# mbed-enablement-platform_F_3.net
KiCad netlist of a schematic drawn in Altium Designer
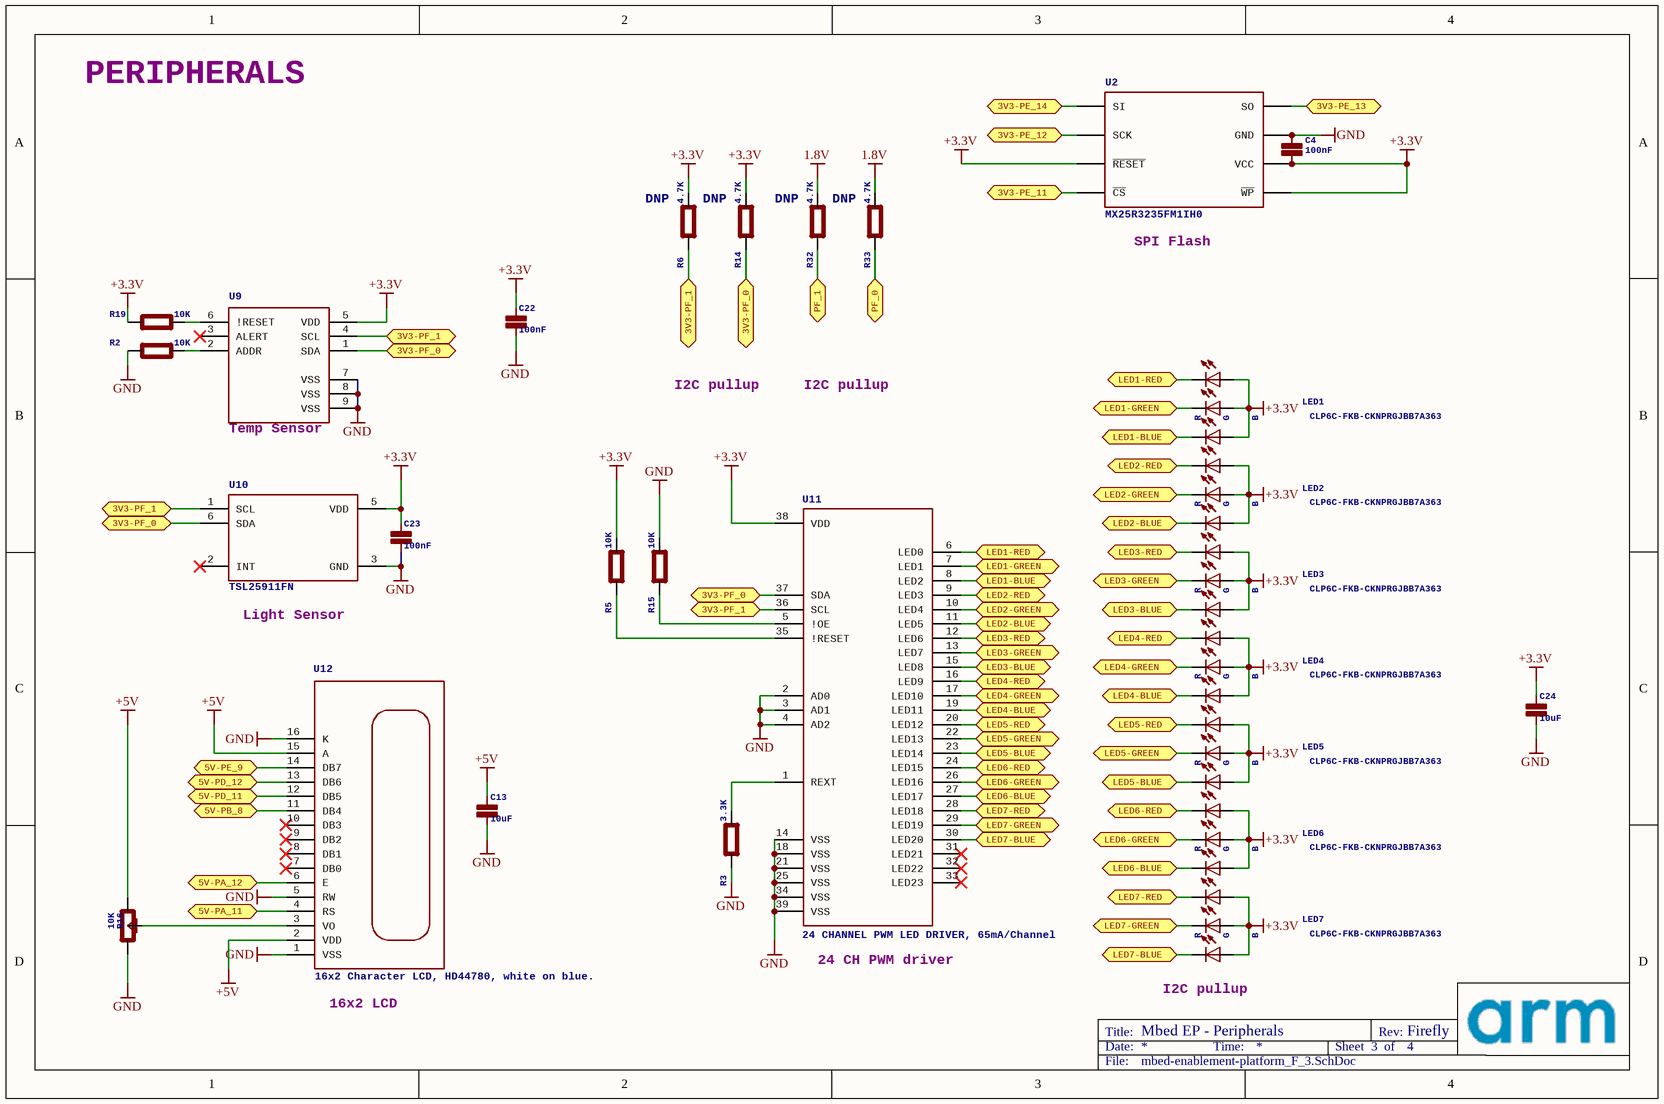
[diagram p0: mbed-enablement-platform_F_3.SchDoc]

(export (version "E")
  (design (tool "Eeschema 10.0.6"))
  (components
    (comp (ref "C4")
      (value "100nF")
      (footprint "0603")
      (description "Capacitor")
      (libsource (lib "mbed-workplace-env-mon") (part "CAPACITOR0603"))
    )
    (comp (ref "C13")
      (value "10uF")
      (footprint "0603")
      (description "Capacitor")
      (libsource (lib "mbed-workplace-env-mon") (part "CAPACITOR0603"))
    )
    (comp (ref "C22")
      (value "100nF")
      (footprint "0402")
      (description "Capacitor")
      (libsource (lib "mbed-workplace-env-mon") (part "CAPACITOR0402"))
    )
    (comp (ref "C23")
      (value "100nF")
      (footprint "0402")
      (description "Capacitor")
      (libsource (lib "mbed-workplace-env-mon") (part "CAPACITOR0402"))
    )
    (comp (ref "C24")
      (value "10uF")
      (footprint "0603")
      (description "Capacitor")
      (libsource (lib "mbed-workplace-env-mon") (part "CAPACITOR0603"))
    )
    (comp (ref "LED1")
      (value "CLP6C-FKB-CKNPRGJBB7A363")
      (footprint "6-PLCC")
      (description "LED RGB SMD Diffused")
      (fields
        (field (name "MF") "Cree Inc.")
        (field (name "B") "B")
        (field (name "R") "R")
        (field (name "G") "G")
      )
      (libsource (lib "mbed-workplace-env-mon") (part "CLP6C-FKB-CKNPRGJBB7A363"))
    )
    (comp (ref "LED2")
      (value "CLP6C-FKB-CKNPRGJBB7A363")
      (footprint "6-PLCC")
      (description "LED RGB SMD Diffused")
      (fields
        (field (name "MF") "Cree Inc.")
        (field (name "B") "B")
        (field (name "R") "R")
        (field (name "G") "G")
      )
      (libsource (lib "mbed-workplace-env-mon") (part "CLP6C-FKB-CKNPRGJBB7A363"))
    )
    (comp (ref "LED3")
      (value "CLP6C-FKB-CKNPRGJBB7A363")
      (footprint "6-PLCC")
      (description "LED RGB SMD Diffused")
      (fields
        (field (name "MF") "Cree Inc.")
        (field (name "B") "B")
        (field (name "R") "R")
        (field (name "G") "G")
      )
      (libsource (lib "mbed-workplace-env-mon") (part "CLP6C-FKB-CKNPRGJBB7A363"))
    )
    (comp (ref "LED4")
      (value "CLP6C-FKB-CKNPRGJBB7A363")
      (footprint "6-PLCC")
      (description "LED RGB SMD Diffused")
      (fields
        (field (name "MF") "Cree Inc.")
        (field (name "B") "B")
        (field (name "R") "R")
        (field (name "G") "G")
      )
      (libsource (lib "mbed-workplace-env-mon") (part "CLP6C-FKB-CKNPRGJBB7A363"))
    )
    (comp (ref "LED5")
      (value "CLP6C-FKB-CKNPRGJBB7A363")
      (footprint "6-PLCC")
      (description "LED RGB SMD Diffused")
      (fields
        (field (name "MF") "Cree Inc.")
        (field (name "B") "B")
        (field (name "R") "R")
        (field (name "G") "G")
      )
      (libsource (lib "mbed-workplace-env-mon") (part "CLP6C-FKB-CKNPRGJBB7A363"))
    )
    (comp (ref "LED6")
      (value "CLP6C-FKB-CKNPRGJBB7A363")
      (footprint "6-PLCC")
      (description "LED RGB SMD Diffused")
      (fields
        (field (name "MF") "Cree Inc.")
        (field (name "B") "B")
        (field (name "R") "R")
        (field (name "G") "G")
      )
      (libsource (lib "mbed-workplace-env-mon") (part "CLP6C-FKB-CKNPRGJBB7A363"))
    )
    (comp (ref "LED7")
      (value "CLP6C-FKB-CKNPRGJBB7A363")
      (footprint "6-PLCC")
      (description "LED RGB SMD Diffused")
      (fields
        (field (name "MF") "Cree Inc.")
        (field (name "B") "B")
        (field (name "R") "R")
        (field (name "G") "G")
      )
      (libsource (lib "mbed-workplace-env-mon") (part "CLP6C-FKB-CKNPRGJBB7A363"))
    )
    (comp (ref "R2")
      (value "10K")
      (footprint "0402")
      (description "Resistor")
      (libsource (lib "mbed-workplace-env-mon") (part "RESISTOR0402"))
    )
    (comp (ref "R3")
      (value "3.3K")
      (footprint "0402")
      (description "Resistor")
      (libsource (lib "mbed-workplace-env-mon") (part "RESISTOR0402"))
    )
    (comp (ref "R5")
      (value "10K")
      (footprint "0402")
      (description "Resistor")
      (libsource (lib "mbed-workplace-env-mon") (part "RESISTOR0402"))
    )
    (comp (ref "R6")
      (value "4.7K")
      (footprint "0402")
      (description "Resistor")
      (libsource (lib "mbed-workplace-env-mon") (part "RESISTOR0402"))
    )
    (comp (ref "R14")
      (value "4.7K")
      (footprint "0402")
      (description "Resistor")
      (libsource (lib "mbed-workplace-env-mon") (part "RESISTOR0402"))
    )
    (comp (ref "R15")
      (value "10K")
      (footprint "0402")
      (description "Resistor")
      (libsource (lib "mbed-workplace-env-mon") (part "RESISTOR0402"))
    )
    (comp (ref "R16")
      (value "10K")
      (footprint "TC33X-2-103E")
      (description "TRIMMER 10K OHM 0.1W SMD")
      (fields (field (name "MF") "Bourns Inc."))
      (libsource (lib "mbed-workplace-env-mon") (part "POTENTIOMETER"))
    )
    (comp (ref "R19")
      (value "10K")
      (footprint "0402")
      (description "Resistor")
      (libsource (lib "mbed-workplace-env-mon") (part "RESISTOR0402"))
    )
    (comp (ref "R32")
      (value "4.7K")
      (footprint "0402")
      (description "Resistor")
      (libsource (lib "mbed-workplace-env-mon") (part "RESISTOR0402"))
    )
    (comp (ref "R33")
      (value "4.7K")
      (footprint "0402")
      (description "Resistor")
      (libsource (lib "mbed-workplace-env-mon") (part "RESISTOR0402"))
    )
    (comp (ref "U2")
      (value "MX25R3235FM1IH0")
      (footprint "SO8")
      (description "Serial Flash 32 Mb 80 Mhz")
      (fields (field (name "MF") "Macronix"))
      (libsource (lib "mbed-workplace-env-mon") (part "MX25R3235FM1IH0"))
    )
    (comp (ref "U9")
      (value "Temperature and Humidity Sensor I2C 2% 8DFN")
      (footprint "8-DFN")
      (fields (field (name "MF") "Sensirion"))
      (libsource (lib "mbed-workplace-env-mon") (part "SHT31-DIS-B"))
    )
    (comp (ref "U10")
      (value "TSL25911FN")
      (footprint "6-WFDFN")
      (description "Sensor Light Digital, High Dynamic Range, 6-WFDFN")
      (fields (field (name "MF") "ams"))
      (libsource (lib "mbed-workplace-env-mon") (part "TSL25911FN"))
    )
    (comp (ref "U11")
      (value "24 CHANNEL PWM LED DRIVER, 65mA/Channel")
      (footprint "HTSSOP38")
      (fields (field (name "MF") "NXP USA Inc."))
      (libsource (lib "mbed-workplace-env-mon") (part "PCA9956BTWY"))
    )
    (comp (ref "U12")
      (value "16x2 Character LCD, HD44780, white on blue.")
      (footprint "LCD1602")
      (fields (field (name "MF") "Adafruit Industries LLC"))
      (libsource (lib "mbed-workplace-env-mon") (part "1528-1502-ND"))
    )
  )
  (nets
    (net (code "1") (name "+3.3V") (class "Default")
      (node (ref "C22") (pin "1") (pinfunction "P$1_1") (pintype "passive"))
      (node (ref "C23") (pin "1") (pinfunction "P$1_1") (pintype "passive"))
      (node (ref "C24") (pin "1") (pinfunction "P$1_1") (pintype "passive"))
      (node (ref "C4") (pin "2") (pinfunction "P$2_2") (pintype "passive"))
      (node (ref "LED1") (pin "1") (pinfunction "1_1") (pintype "passive"))
      (node (ref "LED1") (pin "2") (pinfunction "2_2") (pintype "passive"))
      (node (ref "LED1") (pin "3") (pinfunction "3_3") (pintype "passive"))
      (node (ref "LED2") (pin "1") (pinfunction "1_1") (pintype "passive"))
      (node (ref "LED2") (pin "2") (pinfunction "2_2") (pintype "passive"))
      (node (ref "LED2") (pin "3") (pinfunction "3_3") (pintype "passive"))
      (node (ref "LED3") (pin "1") (pinfunction "1_1") (pintype "passive"))
      (node (ref "LED3") (pin "2") (pinfunction "2_2") (pintype "passive"))
      (node (ref "LED3") (pin "3") (pinfunction "3_3") (pintype "passive"))
      (node (ref "LED4") (pin "1") (pinfunction "1_1") (pintype "passive"))
      (node (ref "LED4") (pin "2") (pinfunction "2_2") (pintype "passive"))
      (node (ref "LED4") (pin "3") (pinfunction "3_3") (pintype "passive"))
      (node (ref "LED5") (pin "1") (pinfunction "1_1") (pintype "passive"))
      (node (ref "LED5") (pin "2") (pinfunction "2_2") (pintype "passive"))
      (node (ref "LED5") (pin "3") (pinfunction "3_3") (pintype "passive"))
      (node (ref "LED6") (pin "1") (pinfunction "1_1") (pintype "passive"))
      (node (ref "LED6") (pin "2") (pinfunction "2_2") (pintype "passive"))
      (node (ref "LED6") (pin "3") (pinfunction "3_3") (pintype "passive"))
      (node (ref "LED7") (pin "1") (pinfunction "1_1") (pintype "passive"))
      (node (ref "LED7") (pin "2") (pinfunction "2_2") (pintype "passive"))
      (node (ref "LED7") (pin "3") (pinfunction "3_3") (pintype "passive"))
      (node (ref "R14") (pin "2") (pinfunction "P$2_2") (pintype "passive"))
      (node (ref "R19") (pin "1") (pinfunction "P$1_1") (pintype "passive"))
      (node (ref "R5") (pin "2") (pinfunction "P$2_2") (pintype "passive"))
      (node (ref "R6") (pin "2") (pinfunction "P$2_2") (pintype "passive"))
      (node (ref "U10") (pin "5") (pinfunction "VDD_5") (pintype "passive"))
      (node (ref "U11") (pin "38") (pinfunction "VDD_38") (pintype "passive"))
      (node (ref "U2") (pin "3") (pinfunction "~{WP}_3") (pintype "passive"))
      (node (ref "U2") (pin "7") (pinfunction "~{RESET}_7") (pintype "passive"))
      (node (ref "U2") (pin "8") (pinfunction "VCC_8") (pintype "passive"))
      (node (ref "U9") (pin "5") (pinfunction "VDD_5") (pintype "passive"))
    )
    (net (code "2") (name "+5V") (class "Default")
      (node (ref "C13") (pin "1") (pinfunction "P$1_1") (pintype "passive"))
      (node (ref "R16") (pin "1") (pinfunction "P$1_1") (pintype "passive"))
      (node (ref "U12") (pin "15") (pinfunction "A_15") (pintype "passive"))
      (node (ref "U12") (pin "2") (pinfunction "VDD_2") (pintype "open_emitter"))
    )
    (net (code "3") (name "/3V3-PE_11") (class "Default")
      (node (ref "U2") (pin "1") (pinfunction "~{CS}_1") (pintype "passive"))
    )
    (net (code "4") (name "/3V3-PE_12") (class "Default")
      (node (ref "U2") (pin "6") (pinfunction "SCK_6") (pintype "passive"))
    )
    (net (code "5") (name "/3V3-PE_13") (class "Default")
      (node (ref "U2") (pin "2") (pinfunction "SO_2") (pintype "passive"))
    )
    (net (code "6") (name "/3V3-PE_14") (class "Default")
      (node (ref "U2") (pin "5") (pinfunction "SI_5") (pintype "passive"))
    )
    (net (code "7") (name "/3V3-PF_0") (class "Default")
      (node (ref "R14") (pin "1") (pinfunction "P$1_1") (pintype "passive"))
      (node (ref "U10") (pin "6") (pinfunction "SDA_6") (pintype "passive"))
      (node (ref "U11") (pin "37") (pinfunction "SDA_37") (pintype "passive"))
      (node (ref "U9") (pin "1") (pinfunction "SDA_1") (pintype "passive"))
    )
    (net (code "8") (name "/3V3-PF_1") (class "Default")
      (node (ref "R6") (pin "1") (pinfunction "P$1_1") (pintype "passive"))
      (node (ref "U10") (pin "1") (pinfunction "SCL_1") (pintype "passive"))
      (node (ref "U11") (pin "36") (pinfunction "SCL_36") (pintype "passive"))
      (node (ref "U9") (pin "4") (pinfunction "SCL_4") (pintype "passive"))
    )
    (net (code "9") (name "/5V-PA_11") (class "Default")
      (node (ref "U12") (pin "4") (pinfunction "RS_4") (pintype "passive"))
    )
    (net (code "10") (name "/5V-PA_12") (class "Default")
      (node (ref "U12") (pin "6") (pinfunction "E_6") (pintype "passive"))
    )
    (net (code "11") (name "/5V-PB_8") (class "Default")
      (node (ref "U12") (pin "11") (pinfunction "DB4_11") (pintype "passive"))
    )
    (net (code "12") (name "/5V-PD_11") (class "Default")
      (node (ref "U12") (pin "12") (pinfunction "DB5_12") (pintype "passive"))
    )
    (net (code "13") (name "/5V-PD_12") (class "Default")
      (node (ref "U12") (pin "13") (pinfunction "DB6_13") (pintype "passive"))
    )
    (net (code "14") (name "/5V-PE_9") (class "Default")
      (node (ref "U12") (pin "14") (pinfunction "DB7_14") (pintype "passive"))
    )
    (net (code "15") (name "/LED1-BLUE") (class "Default")
      (node (ref "LED1") (pin "4") (pinfunction "4_4") (pintype "passive"))
      (node (ref "U11") (pin "8") (pinfunction "LED2_8") (pintype "passive"))
    )
    (net (code "16") (name "/LED1-GREEN") (class "Default")
      (node (ref "LED1") (pin "5") (pinfunction "5_5") (pintype "passive"))
      (node (ref "U11") (pin "7") (pinfunction "LED1_7") (pintype "passive"))
    )
    (net (code "17") (name "/LED1-RED") (class "Default")
      (node (ref "LED1") (pin "6") (pinfunction "6_6") (pintype "passive"))
      (node (ref "U11") (pin "6") (pinfunction "LED0_6") (pintype "passive"))
    )
    (net (code "18") (name "/LED2-BLUE") (class "Default")
      (node (ref "LED2") (pin "4") (pinfunction "4_4") (pintype "passive"))
      (node (ref "U11") (pin "11") (pinfunction "LED5_11") (pintype "passive"))
    )
    (net (code "19") (name "/LED2-GREEN") (class "Default")
      (node (ref "LED2") (pin "5") (pinfunction "5_5") (pintype "passive"))
      (node (ref "U11") (pin "10") (pinfunction "LED4_10") (pintype "passive"))
    )
    (net (code "20") (name "/LED2-RED") (class "Default")
      (node (ref "LED2") (pin "6") (pinfunction "6_6") (pintype "passive"))
      (node (ref "U11") (pin "9") (pinfunction "LED3_9") (pintype "passive"))
    )
    (net (code "21") (name "/LED3-BLUE") (class "Default")
      (node (ref "LED3") (pin "4") (pinfunction "4_4") (pintype "passive"))
      (node (ref "U11") (pin "15") (pinfunction "LED8_15") (pintype "passive"))
    )
    (net (code "22") (name "/LED3-GREEN") (class "Default")
      (node (ref "LED3") (pin "5") (pinfunction "5_5") (pintype "passive"))
      (node (ref "U11") (pin "13") (pinfunction "LED7_13") (pintype "passive"))
    )
    (net (code "23") (name "/LED3-RED") (class "Default")
      (node (ref "LED3") (pin "6") (pinfunction "6_6") (pintype "passive"))
      (node (ref "U11") (pin "12") (pinfunction "LED6_12") (pintype "passive"))
    )
    (net (code "24") (name "/LED4-BLUE") (class "Default")
      (node (ref "LED4") (pin "4") (pinfunction "4_4") (pintype "passive"))
      (node (ref "U11") (pin "19") (pinfunction "LED11_19") (pintype "passive"))
    )
    (net (code "25") (name "/LED4-GREEN") (class "Default")
      (node (ref "LED4") (pin "5") (pinfunction "5_5") (pintype "passive"))
      (node (ref "U11") (pin "17") (pinfunction "LED10_17") (pintype "passive"))
    )
    (net (code "26") (name "/LED4-RED") (class "Default")
      (node (ref "LED4") (pin "6") (pinfunction "6_6") (pintype "passive"))
      (node (ref "U11") (pin "16") (pinfunction "LED9_16") (pintype "passive"))
    )
    (net (code "27") (name "/LED5-BLUE") (class "Default")
      (node (ref "LED5") (pin "4") (pinfunction "4_4") (pintype "passive"))
      (node (ref "U11") (pin "23") (pinfunction "LED14_23") (pintype "passive"))
    )
    (net (code "28") (name "/LED5-GREEN") (class "Default")
      (node (ref "LED5") (pin "5") (pinfunction "5_5") (pintype "passive"))
      (node (ref "U11") (pin "22") (pinfunction "LED13_22") (pintype "passive"))
    )
    (net (code "29") (name "/LED5-RED") (class "Default")
      (node (ref "LED5") (pin "6") (pinfunction "6_6") (pintype "passive"))
      (node (ref "U11") (pin "20") (pinfunction "LED12_20") (pintype "passive"))
    )
    (net (code "30") (name "/LED6-BLUE") (class "Default")
      (node (ref "LED6") (pin "4") (pinfunction "4_4") (pintype "passive"))
      (node (ref "U11") (pin "27") (pinfunction "LED17_27") (pintype "passive"))
    )
    (net (code "31") (name "/LED6-GREEN") (class "Default")
      (node (ref "LED6") (pin "5") (pinfunction "5_5") (pintype "passive"))
      (node (ref "U11") (pin "26") (pinfunction "LED16_26") (pintype "passive"))
    )
    (net (code "32") (name "/LED6-RED") (class "Default")
      (node (ref "LED6") (pin "6") (pinfunction "6_6") (pintype "passive"))
      (node (ref "U11") (pin "24") (pinfunction "LED15_24") (pintype "passive"))
    )
    (net (code "33") (name "/LED7-BLUE") (class "Default")
      (node (ref "LED7") (pin "4") (pinfunction "4_4") (pintype "passive"))
      (node (ref "U11") (pin "30") (pinfunction "LED20_30") (pintype "passive"))
    )
    (net (code "34") (name "/LED7-GREEN") (class "Default")
      (node (ref "LED7") (pin "5") (pinfunction "5_5") (pintype "passive"))
      (node (ref "U11") (pin "29") (pinfunction "LED19_29") (pintype "passive"))
    )
    (net (code "35") (name "/LED7-RED") (class "Default")
      (node (ref "LED7") (pin "6") (pinfunction "6_6") (pintype "passive"))
      (node (ref "U11") (pin "28") (pinfunction "LED18_28") (pintype "passive"))
    )
    (net (code "36") (name "/PF_0") (class "Default")
      (node (ref "R33") (pin "1") (pinfunction "P$1_1") (pintype "passive"))
    )
    (net (code "37") (name "/PF_1") (class "Default")
      (node (ref "R32") (pin "1") (pinfunction "P$1_1") (pintype "passive"))
    )
    (net (code "38") (name "1.8V") (class "Default")
      (node (ref "R32") (pin "2") (pinfunction "P$2_2") (pintype "passive"))
      (node (ref "R33") (pin "2") (pinfunction "P$2_2") (pintype "passive"))
    )
    (net (code "39") (name "GND") (class "Default")
      (node (ref "C13") (pin "2") (pinfunction "P$2_2") (pintype "passive"))
      (node (ref "C22") (pin "2") (pinfunction "P$2_2") (pintype "passive"))
      (node (ref "C23") (pin "2") (pinfunction "P$2_2") (pintype "passive"))
      (node (ref "C24") (pin "2") (pinfunction "P$2_2") (pintype "passive"))
      (node (ref "C4") (pin "1") (pinfunction "P$1_1") (pintype "passive"))
      (node (ref "R15") (pin "2") (pinfunction "P$2_2") (pintype "passive"))
      (node (ref "R16") (pin "3") (pinfunction "P$3_3") (pintype "passive"))
      (node (ref "R2") (pin "1") (pinfunction "P$1_1") (pintype "passive"))
      (node (ref "R3") (pin "1") (pinfunction "P$1_1") (pintype "passive"))
      (node (ref "U10") (pin "3") (pinfunction "GND_3") (pintype "passive"))
      (node (ref "U11") (pin "14") (pinfunction "VSS_14") (pintype "passive"))
      (node (ref "U11") (pin "18") (pinfunction "VSS_18") (pintype "passive"))
      (node (ref "U11") (pin "2") (pinfunction "AD0_2") (pintype "passive"))
      (node (ref "U11") (pin "21") (pinfunction "VSS_21") (pintype "passive"))
      (node (ref "U11") (pin "25") (pinfunction "VSS_25") (pintype "passive"))
      (node (ref "U11") (pin "3") (pinfunction "AD1_3") (pintype "passive"))
      (node (ref "U11") (pin "34") (pinfunction "VSS_34") (pintype "passive"))
      (node (ref "U11") (pin "39") (pinfunction "VSS_39") (pintype "passive"))
      (node (ref "U11") (pin "4") (pinfunction "AD2_4") (pintype "passive"))
      (node (ref "U12") (pin "1") (pinfunction "VSS_1") (pintype "power_in"))
      (node (ref "U12") (pin "16") (pinfunction "K_16") (pintype "passive"))
      (node (ref "U12") (pin "5") (pinfunction "RW_5") (pintype "passive"))
      (node (ref "U2") (pin "4") (pinfunction "GND_4") (pintype "passive"))
      (node (ref "U9") (pin "7") (pinfunction "VSS_7") (pintype "passive"))
      (node (ref "U9") (pin "8") (pinfunction "VSS_8") (pintype "passive"))
      (node (ref "U9") (pin "9") (pinfunction "VSS_9") (pintype "passive"))
    )
    (net (code "40") (name "Net-(R2-P$2)") (class "Default")
      (node (ref "R2") (pin "2") (pinfunction "P$2_2") (pintype "passive"))
      (node (ref "U9") (pin "2") (pinfunction "ADDR_2") (pintype "passive"))
    )
    (net (code "41") (name "Net-(R3-P$2)") (class "Default")
      (node (ref "R3") (pin "2") (pinfunction "P$2_2") (pintype "passive"))
      (node (ref "U11") (pin "1") (pinfunction "REXT_1") (pintype "passive"))
    )
    (net (code "42") (name "Net-(R5-P$1)") (class "Default")
      (node (ref "R5") (pin "1") (pinfunction "P$1_1") (pintype "passive"))
      (node (ref "U11") (pin "35") (pinfunction "!RESET_35") (pintype "passive"))
    )
    (net (code "43") (name "Net-(R15-P$1)") (class "Default")
      (node (ref "R15") (pin "1") (pinfunction "P$1_1") (pintype "passive"))
      (node (ref "U11") (pin "5") (pinfunction "!OE_5") (pintype "passive"))
    )
    (net (code "44") (name "Net-(R16-P$2)") (class "Default")
      (node (ref "R16") (pin "2") (pinfunction "P$2_2") (pintype "passive"))
      (node (ref "U12") (pin "3") (pinfunction "VO_3") (pintype "passive"))
    )
    (net (code "45") (name "Net-(R19-P$2)") (class "Default")
      (node (ref "R19") (pin "2") (pinfunction "P$2_2") (pintype "passive"))
      (node (ref "U9") (pin "6") (pinfunction "!RESET_6") (pintype "passive"))
    )
    (net (code "46") (name "unconnected-(U9-ALERT-Pad3)") (class "Default")
      (node (ref "U9") (pin "3") (pinfunction "ALERT_3") (pintype "passive+no_connect"))
    )
    (net (code "47") (name "unconnected-(U10-INT-Pad2)") (class "Default")
      (node (ref "U10") (pin "2") (pinfunction "INT_2") (pintype "passive+no_connect"))
    )
    (net (code "48") (name "unconnected-(U11-LED21-Pad31)") (class "Default")
      (node (ref "U11") (pin "31") (pinfunction "LED21_31") (pintype "passive+no_connect"))
    )
    (net (code "49") (name "unconnected-(U11-LED22-Pad32)") (class "Default")
      (node (ref "U11") (pin "32") (pinfunction "LED22_32") (pintype "passive+no_connect"))
    )
    (net (code "50") (name "unconnected-(U11-LED23-Pad33)") (class "Default")
      (node (ref "U11") (pin "33") (pinfunction "LED23_33") (pintype "passive+no_connect"))
    )
    (net (code "51") (name "unconnected-(U12-DB0-Pad7)") (class "Default")
      (node (ref "U12") (pin "7") (pinfunction "DB0_7") (pintype "passive+no_connect"))
    )
    (net (code "52") (name "unconnected-(U12-DB1-Pad8)") (class "Default")
      (node (ref "U12") (pin "8") (pinfunction "DB1_8") (pintype "passive+no_connect"))
    )
    (net (code "53") (name "unconnected-(U12-DB2-Pad9)") (class "Default")
      (node (ref "U12") (pin "9") (pinfunction "DB2_9") (pintype "passive+no_connect"))
    )
    (net (code "54") (name "unconnected-(U12-DB3-Pad10)") (class "Default")
      (node (ref "U12") (pin "10") (pinfunction "DB3_10") (pintype "passive+no_connect"))
    )
  )
)
